# PPM2DSM_fix.net
KiCad netlist of a schematic drawn in EAGLE
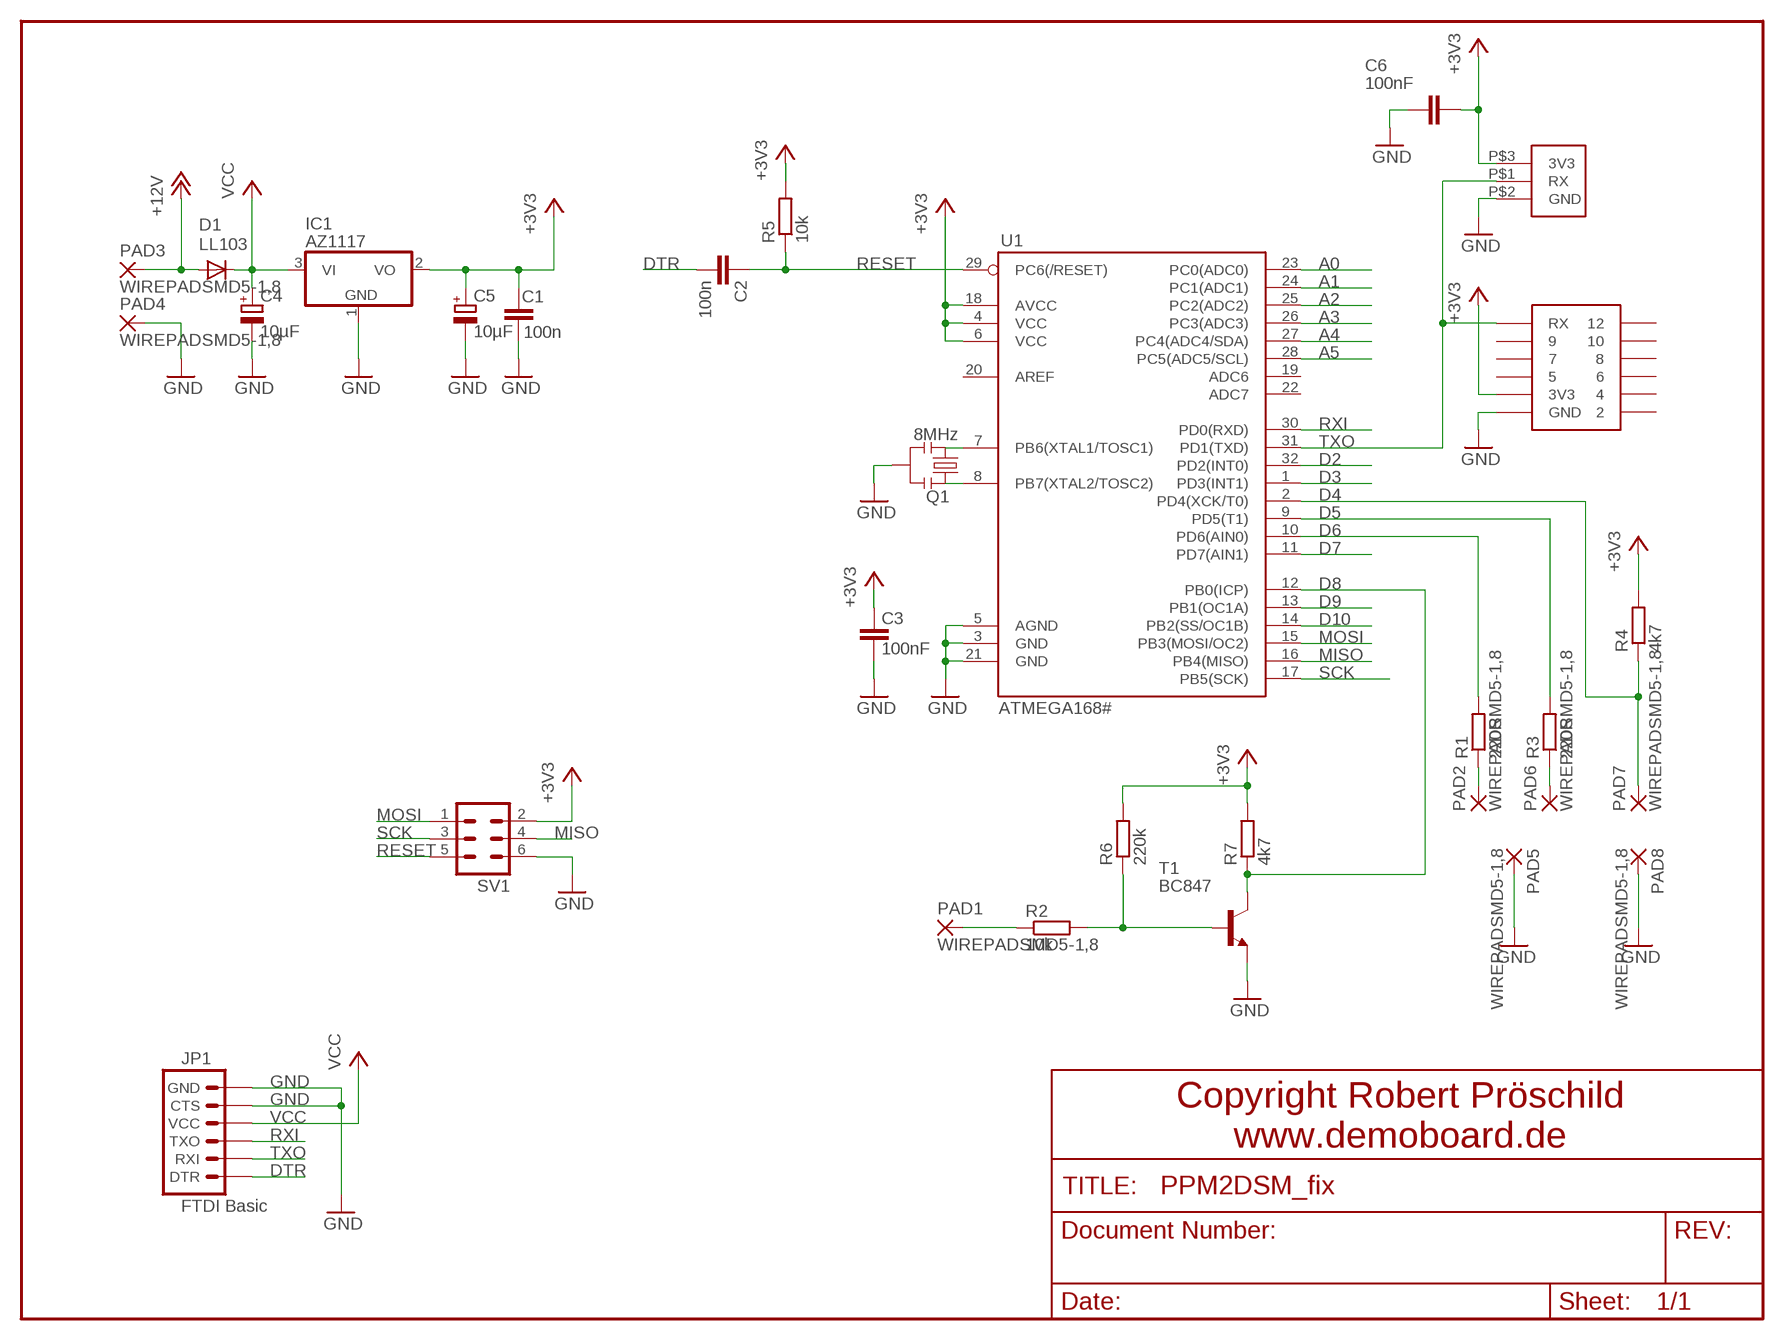
[diagram p0: schematic, sheet 1]

(export (version "E")
  (design (tool "Eeschema 10.0.6"))
  (components
    (comp (ref "C1")
      (value "100n")
      (footprint "eagle-import:C0805")
      (libsource (lib "eagle-import") (part "C-EUC0805"))
    )
    (comp (ref "C2")
      (value "100n")
      (footprint "eagle-import:C0805")
      (libsource (lib "eagle-import") (part "C-EUC0805"))
    )
    (comp (ref "C3")
      (value "100nF")
      (footprint "eagle-import:C0805")
      (libsource (lib "eagle-import") (part "C-EUC0805"))
    )
    (comp (ref "C4")
      (value "10µF")
      (footprint "eagle-import:CT6032")
      (libsource (lib "eagle-import") (part "CPOL-EUCT6032"))
    )
    (comp (ref "C5")
      (value "10µF")
      (footprint "eagle-import:CT6032")
      (libsource (lib "eagle-import") (part "CPOL-EUCT6032"))
    )
    (comp (ref "C6")
      (value "100nF")
      (footprint "eagle-import:C0805")
      (libsource (lib "eagle-import") (part "C-EUC0805"))
    )
    (comp (ref "D1")
      (value "LL103")
      (footprint "eagle-import:MINIMELF")
      (libsource (lib "eagle-import") (part "DIODE-MINIMELF"))
    )
    (comp (ref "IC1")
      (value "AZ1117")
      (footprint "eagle-import:SOT223")
      (libsource (lib "eagle-import") (part "AZ1117"))
    )
    (comp (ref "IC2")
      (value "X10EMTX")
      (footprint "eagle-import:X10EMTX")
      (libsource (lib "eagle-import") (part "X10EMTX"))
    )
    (comp (ref "IC3")
      (value "X1TX0")
      (footprint "eagle-import:X1TX0")
      (libsource (lib "eagle-import") (part "X1TX0"))
    )
    (comp (ref "JP1")
      (value "FTDI Basic")
      (footprint "eagle-import:1X06")
      (libsource (lib "eagle-import") (part "ARDUINO_SERIAL_PROGRAMPTH"))
    )
    (comp (ref "PAD1")
      (value "WIREPADSMD5-1,8")
      (footprint "eagle-import:5-1,8")
      (libsource (lib "eagle-import") (part "WIREPADSMD5-1,8"))
    )
    (comp (ref "PAD2")
      (value "WIREPADSMD5-1,8")
      (footprint "eagle-import:5-1,8")
      (libsource (lib "eagle-import") (part "WIREPADSMD5-1,8"))
    )
    (comp (ref "PAD3")
      (value "WIREPADSMD5-1,8")
      (footprint "eagle-import:5-1,8")
      (libsource (lib "eagle-import") (part "WIREPADSMD5-1,8"))
    )
    (comp (ref "PAD4")
      (value "WIREPADSMD5-1,8")
      (footprint "eagle-import:5-1,8")
      (libsource (lib "eagle-import") (part "WIREPADSMD5-1,8"))
    )
    (comp (ref "PAD5")
      (value "WIREPADSMD5-1,8")
      (footprint "eagle-import:5-1,8")
      (libsource (lib "eagle-import") (part "WIREPADSMD5-1,8"))
    )
    (comp (ref "PAD6")
      (value "WIREPADSMD5-1,8")
      (footprint "eagle-import:5-1,8")
      (libsource (lib "eagle-import") (part "WIREPADSMD5-1,8"))
    )
    (comp (ref "PAD7")
      (value "WIREPADSMD5-1,8")
      (footprint "eagle-import:5-1,8")
      (libsource (lib "eagle-import") (part "WIREPADSMD5-1,8"))
    )
    (comp (ref "PAD8")
      (value "WIREPADSMD5-1,8")
      (footprint "eagle-import:5-1,8")
      (libsource (lib "eagle-import") (part "WIREPADSMD5-1,8"))
    )
    (comp (ref "Q1")
      (value "8MHz")
      (footprint "eagle-import:RESONATOR-SMD")
      (libsource (lib "eagle-import") (part "RESONATORSMD"))
    )
    (comp (ref "R1")
      (value "220R")
      (footprint "eagle-import:R0805")
      (libsource (lib "eagle-import") (part "R-EU_R0805"))
    )
    (comp (ref "R2")
      (value "10k")
      (footprint "eagle-import:R0805")
      (libsource (lib "eagle-import") (part "R-EU_R0805"))
    )
    (comp (ref "R3")
      (value "220R")
      (footprint "eagle-import:R0805")
      (libsource (lib "eagle-import") (part "R-EU_R0805"))
    )
    (comp (ref "R4")
      (value "4k7")
      (footprint "eagle-import:R0805")
      (libsource (lib "eagle-import") (part "R-EU_R0805"))
    )
    (comp (ref "R5")
      (value "10k")
      (footprint "eagle-import:R0805")
      (libsource (lib "eagle-import") (part "R-EU_R0805"))
    )
    (comp (ref "R6")
      (value "220k")
      (footprint "eagle-import:R0805")
      (libsource (lib "eagle-import") (part "R-EU_R0805"))
    )
    (comp (ref "R7")
      (value "4k7")
      (footprint "eagle-import:R0805")
      (libsource (lib "eagle-import") (part "R-EU_R0805"))
    )
    (comp (ref "SV1")
      (value "MA03-2")
      (footprint "eagle-import:MA03-2")
      (libsource (lib "eagle-import") (part "MA03-2"))
    )
    (comp (ref "T1")
      (value "BC847")
      (footprint "eagle-import:SOT23")
      (libsource (lib "eagle-import") (part "BC847"))
    )
    (comp (ref "U1")
      (value "ATMEGA168#")
      (footprint "eagle-import:TQFP32-08")
      (libsource (lib "eagle-import") (part "ATMEGA168"))
    )
  )
  (nets
    (net (code "1") (name "+3V3") (class "Default")
      (node (ref "C1") (pin "2") (pinfunction "2_2") (pintype "passive"))
      (node (ref "C3") (pin "2") (pinfunction "2_2") (pintype "passive"))
      (node (ref "C5") (pin "+") (pinfunction "+_+") (pintype "passive"))
      (node (ref "C6") (pin "2") (pinfunction "2_2") (pintype "passive"))
      (node (ref "IC1") (pin "2") (pinfunction "VO_2") (pintype "passive"))
      (node (ref "IC2") (pin "P$3") (pinfunction "3V3_P$3") (pintype "power_in"))
      (node (ref "IC3") (pin "3") (pinfunction "3V3_3") (pintype "bidirectional"))
      (node (ref "R4") (pin "2") (pinfunction "2_2") (pintype "passive"))
      (node (ref "R5") (pin "2") (pinfunction "2_2") (pintype "passive"))
      (node (ref "R6") (pin "2") (pinfunction "2_2") (pintype "passive"))
      (node (ref "R7") (pin "2") (pinfunction "2_2") (pintype "passive"))
      (node (ref "SV1") (pin "2") (pinfunction "2_2") (pintype "passive"))
      (node (ref "U1") (pin "18") (pinfunction "AVCC_18") (pintype "bidirectional"))
      (node (ref "U1") (pin "4") (pinfunction "VCC_4") (pintype "bidirectional"))
      (node (ref "U1") (pin "6") (pinfunction "VCC_6") (pintype "bidirectional"))
    )
    (net (code "2") (name "+12V") (class "Default")
      (node (ref "D1") (pin "A") (pinfunction "A_A") (pintype "passive"))
      (node (ref "PAD3") (pin "1") (pinfunction "P_1") (pintype "passive"))
    )
    (net (code "3") (name "/2") (class "Default")
      (node (ref "IC3") (pin "2") (pinfunction "2_2") (pintype "power_in"))
    )
    (net (code "4") (name "/4") (class "Default")
      (node (ref "IC3") (pin "4") (pinfunction "4_4") (pintype "power_in"))
    )
    (net (code "5") (name "/A0") (class "Default")
      (node (ref "U1") (pin "23") (pinfunction "PC0(ADC0)_23") (pintype "bidirectional"))
    )
    (net (code "6") (name "/A1") (class "Default")
      (node (ref "U1") (pin "24") (pinfunction "PC1(ADC1)_24") (pintype "bidirectional"))
    )
    (net (code "7") (name "/A2") (class "Default")
      (node (ref "U1") (pin "25") (pinfunction "PC2(ADC2)_25") (pintype "bidirectional"))
    )
    (net (code "8") (name "/A3") (class "Default")
      (node (ref "U1") (pin "26") (pinfunction "PC3(ADC3)_26") (pintype "bidirectional"))
    )
    (net (code "9") (name "/A4") (class "Default")
      (node (ref "U1") (pin "27") (pinfunction "PC4(ADC4/SDA)_27") (pintype "bidirectional"))
    )
    (net (code "10") (name "/A5") (class "Default")
      (node (ref "U1") (pin "28") (pinfunction "PC5(ADC5/SCL)_28") (pintype "bidirectional"))
    )
    (net (code "11") (name "/D2") (class "Default")
      (node (ref "U1") (pin "32") (pinfunction "PD2(INT0)_32") (pintype "bidirectional"))
    )
    (net (code "12") (name "/D3") (class "Default")
      (node (ref "U1") (pin "1") (pinfunction "PD3(INT1)_1") (pintype "bidirectional"))
    )
    (net (code "13") (name "/D4") (class "Default")
      (node (ref "PAD7") (pin "1") (pinfunction "P_1") (pintype "passive"))
      (node (ref "R4") (pin "1") (pinfunction "1_1") (pintype "passive"))
      (node (ref "U1") (pin "2") (pinfunction "PD4(XCK/T0)_2") (pintype "bidirectional"))
    )
    (net (code "14") (name "/D5") (class "Default")
      (node (ref "R3") (pin "2") (pinfunction "2_2") (pintype "passive"))
      (node (ref "U1") (pin "9") (pinfunction "PD5(T1)_9") (pintype "bidirectional"))
    )
    (net (code "15") (name "/D6") (class "Default")
      (node (ref "R1") (pin "2") (pinfunction "2_2") (pintype "passive"))
      (node (ref "U1") (pin "10") (pinfunction "PD6(AIN0)_10") (pintype "bidirectional"))
    )
    (net (code "16") (name "/D7") (class "Default")
      (node (ref "U1") (pin "11") (pinfunction "PD7(AIN1)_11") (pintype "bidirectional"))
    )
    (net (code "17") (name "/D8") (class "Default")
      (node (ref "R7") (pin "1") (pinfunction "1_1") (pintype "passive"))
      (node (ref "T1") (pin "3") (pinfunction "C_3") (pintype "passive"))
      (node (ref "U1") (pin "12") (pinfunction "PB0(ICP)_12") (pintype "bidirectional"))
    )
    (net (code "18") (name "/D9") (class "Default")
      (node (ref "U1") (pin "13") (pinfunction "PB1(OC1A)_13") (pintype "bidirectional"))
    )
    (net (code "19") (name "/D10") (class "Default")
      (node (ref "U1") (pin "14") (pinfunction "PB2(SS/OC1B)_14") (pintype "bidirectional"))
    )
    (net (code "20") (name "/DTR") (class "Default")
      (node (ref "C2") (pin "2") (pinfunction "2_2") (pintype "passive"))
      (node (ref "JP1") (pin "1") (pinfunction "DTR_1") (pintype "passive"))
    )
    (net (code "21") (name "/MISO") (class "Default")
      (node (ref "SV1") (pin "4") (pinfunction "4_4") (pintype "passive"))
      (node (ref "U1") (pin "16") (pinfunction "PB4(MISO)_16") (pintype "bidirectional"))
    )
    (net (code "22") (name "/MOSI") (class "Default")
      (node (ref "SV1") (pin "1") (pinfunction "1_1") (pintype "passive"))
      (node (ref "U1") (pin "15") (pinfunction "PB3(MOSI/OC2)_15") (pintype "bidirectional"))
    )
    (net (code "23") (name "/RESET") (class "Default")
      (node (ref "C2") (pin "1") (pinfunction "1_1") (pintype "passive"))
      (node (ref "R5") (pin "1") (pinfunction "1_1") (pintype "passive"))
      (node (ref "SV1") (pin "5") (pinfunction "5_5") (pintype "passive"))
      (node (ref "U1") (pin "29") (pinfunction "PC6(/RESET)_29") (pintype "bidirectional"))
    )
    (net (code "24") (name "/RXI") (class "Default")
      (node (ref "JP1") (pin "3") (pinfunction "TXO_3") (pintype "passive"))
      (node (ref "U1") (pin "30") (pinfunction "PD0(RXD)_30") (pintype "bidirectional"))
    )
    (net (code "25") (name "/SCK") (class "Default")
      (node (ref "SV1") (pin "3") (pinfunction "3_3") (pintype "passive"))
      (node (ref "U1") (pin "17") (pinfunction "PB5(SCK)_17") (pintype "bidirectional"))
    )
    (net (code "26") (name "/TXO") (class "Default")
      (node (ref "IC2") (pin "P$1") (pinfunction "RX_P$1") (pintype "input"))
      (node (ref "IC3") (pin "11") (pinfunction "RX_11") (pintype "bidirectional"))
      (node (ref "JP1") (pin "2") (pinfunction "RXI_2") (pintype "passive"))
      (node (ref "U1") (pin "31") (pinfunction "PD1(TXD)_31") (pintype "bidirectional"))
    )
    (net (code "27") (name "GND") (class "Default")
      (node (ref "C1") (pin "1") (pinfunction "1_1") (pintype "passive"))
      (node (ref "C3") (pin "1") (pinfunction "1_1") (pintype "passive"))
      (node (ref "C4") (pin "-") (pinfunction "-_-") (pintype "passive"))
      (node (ref "C5") (pin "-") (pinfunction "-_-") (pintype "passive"))
      (node (ref "C6") (pin "1") (pinfunction "1_1") (pintype "passive"))
      (node (ref "IC1") (pin "1") (pinfunction "GND_1") (pintype "passive"))
      (node (ref "IC2") (pin "P$2") (pinfunction "GND_P$2") (pintype "power_in"))
      (node (ref "IC3") (pin "1") (pinfunction "GND_1") (pintype "bidirectional"))
      (node (ref "JP1") (pin "5") (pinfunction "CTS_5") (pintype "passive"))
      (node (ref "JP1") (pin "6") (pinfunction "GND_6") (pintype "passive"))
      (node (ref "PAD4") (pin "1") (pinfunction "P_1") (pintype "passive"))
      (node (ref "PAD5") (pin "1") (pinfunction "P_1") (pintype "passive"))
      (node (ref "PAD8") (pin "1") (pinfunction "P_1") (pintype "passive"))
      (node (ref "Q1") (pin "2") (pinfunction "2_2") (pintype "passive"))
      (node (ref "SV1") (pin "6") (pinfunction "6_6") (pintype "passive"))
      (node (ref "T1") (pin "2") (pinfunction "E_2") (pintype "passive"))
      (node (ref "U1") (pin "21") (pinfunction "GND_21") (pintype "bidirectional"))
      (node (ref "U1") (pin "3") (pinfunction "GND_3") (pintype "bidirectional"))
      (node (ref "U1") (pin "5") (pinfunction "AGND_5") (pintype "bidirectional"))
    )
    (net (code "28") (name "Net-(PAD1-P)") (class "Default")
      (node (ref "PAD1") (pin "1") (pinfunction "P_1") (pintype "passive"))
      (node (ref "R2") (pin "1") (pinfunction "1_1") (pintype "passive"))
    )
    (net (code "29") (name "Net-(PAD2-P)") (class "Default")
      (node (ref "PAD2") (pin "1") (pinfunction "P_1") (pintype "passive"))
      (node (ref "R1") (pin "1") (pinfunction "1_1") (pintype "passive"))
    )
    (net (code "30") (name "Net-(PAD6-P)") (class "Default")
      (node (ref "PAD6") (pin "1") (pinfunction "P_1") (pintype "passive"))
      (node (ref "R3") (pin "1") (pinfunction "1_1") (pintype "passive"))
    )
    (net (code "31") (name "Net-(T1-B)") (class "Default")
      (node (ref "R2") (pin "2") (pinfunction "2_2") (pintype "passive"))
      (node (ref "R6") (pin "1") (pinfunction "1_1") (pintype "passive"))
      (node (ref "T1") (pin "1") (pinfunction "B_1") (pintype "passive"))
    )
    (net (code "32") (name "Net-(U1-PB6(XTAL1{slash}TOSC1))") (class "Default")
      (node (ref "Q1") (pin "3") (pinfunction "3_3") (pintype "passive"))
      (node (ref "U1") (pin "7") (pinfunction "PB6(XTAL1/TOSC1)_7") (pintype "bidirectional"))
    )
    (net (code "33") (name "Net-(U1-PB7(XTAL2{slash}TOSC2))") (class "Default")
      (node (ref "Q1") (pin "1") (pinfunction "1_1") (pintype "passive"))
      (node (ref "U1") (pin "8") (pinfunction "PB7(XTAL2/TOSC2)_8") (pintype "bidirectional"))
    )
    (net (code "34") (name "VCC") (class "Default")
      (node (ref "C4") (pin "+") (pinfunction "+_+") (pintype "passive"))
      (node (ref "D1") (pin "C") (pinfunction "C_C") (pintype "passive"))
      (node (ref "IC1") (pin "3") (pinfunction "VI_3") (pintype "input"))
      (node (ref "JP1") (pin "4") (pinfunction "VCC_4") (pintype "passive"))
    )
    (net (code "35") (name "unconnected-(IC3-Pad5)") (class "Default")
      (node (ref "IC3") (pin "5") (pinfunction "5_5") (pintype "bidirectional"))
    )
    (net (code "36") (name "unconnected-(IC3-Pad6)") (class "Default")
      (node (ref "IC3") (pin "6") (pinfunction "6_6") (pintype "bidirectional"))
    )
    (net (code "37") (name "unconnected-(IC3-Pad7)") (class "Default")
      (node (ref "IC3") (pin "7") (pinfunction "7_7") (pintype "bidirectional"))
    )
    (net (code "38") (name "unconnected-(IC3-Pad8)") (class "Default")
      (node (ref "IC3") (pin "8") (pinfunction "8_8") (pintype "bidirectional"))
    )
    (net (code "39") (name "unconnected-(IC3-Pad9)") (class "Default")
      (node (ref "IC3") (pin "9") (pinfunction "9_9") (pintype "bidirectional"))
    )
    (net (code "40") (name "unconnected-(IC3-Pad10)") (class "Default")
      (node (ref "IC3") (pin "10") (pinfunction "10_10") (pintype "bidirectional"))
    )
    (net (code "41") (name "unconnected-(IC3-Pad12)") (class "Default")
      (node (ref "IC3") (pin "12") (pinfunction "12_12") (pintype "input"))
    )
    (net (code "42") (name "unconnected-(U1-ADC6-Pad19)") (class "Default")
      (node (ref "U1") (pin "19") (pinfunction "ADC6_19") (pintype "bidirectional"))
    )
    (net (code "43") (name "unconnected-(U1-ADC7-Pad22)") (class "Default")
      (node (ref "U1") (pin "22") (pinfunction "ADC7_22") (pintype "bidirectional"))
    )
    (net (code "44") (name "unconnected-(U1-AREF-Pad20)") (class "Default")
      (node (ref "U1") (pin "20") (pinfunction "AREF_20") (pintype "bidirectional"))
    )
  )
)
